# 2_DDR3L_16bits.net
KiCad netlist of a schematic drawn in Altium Designer
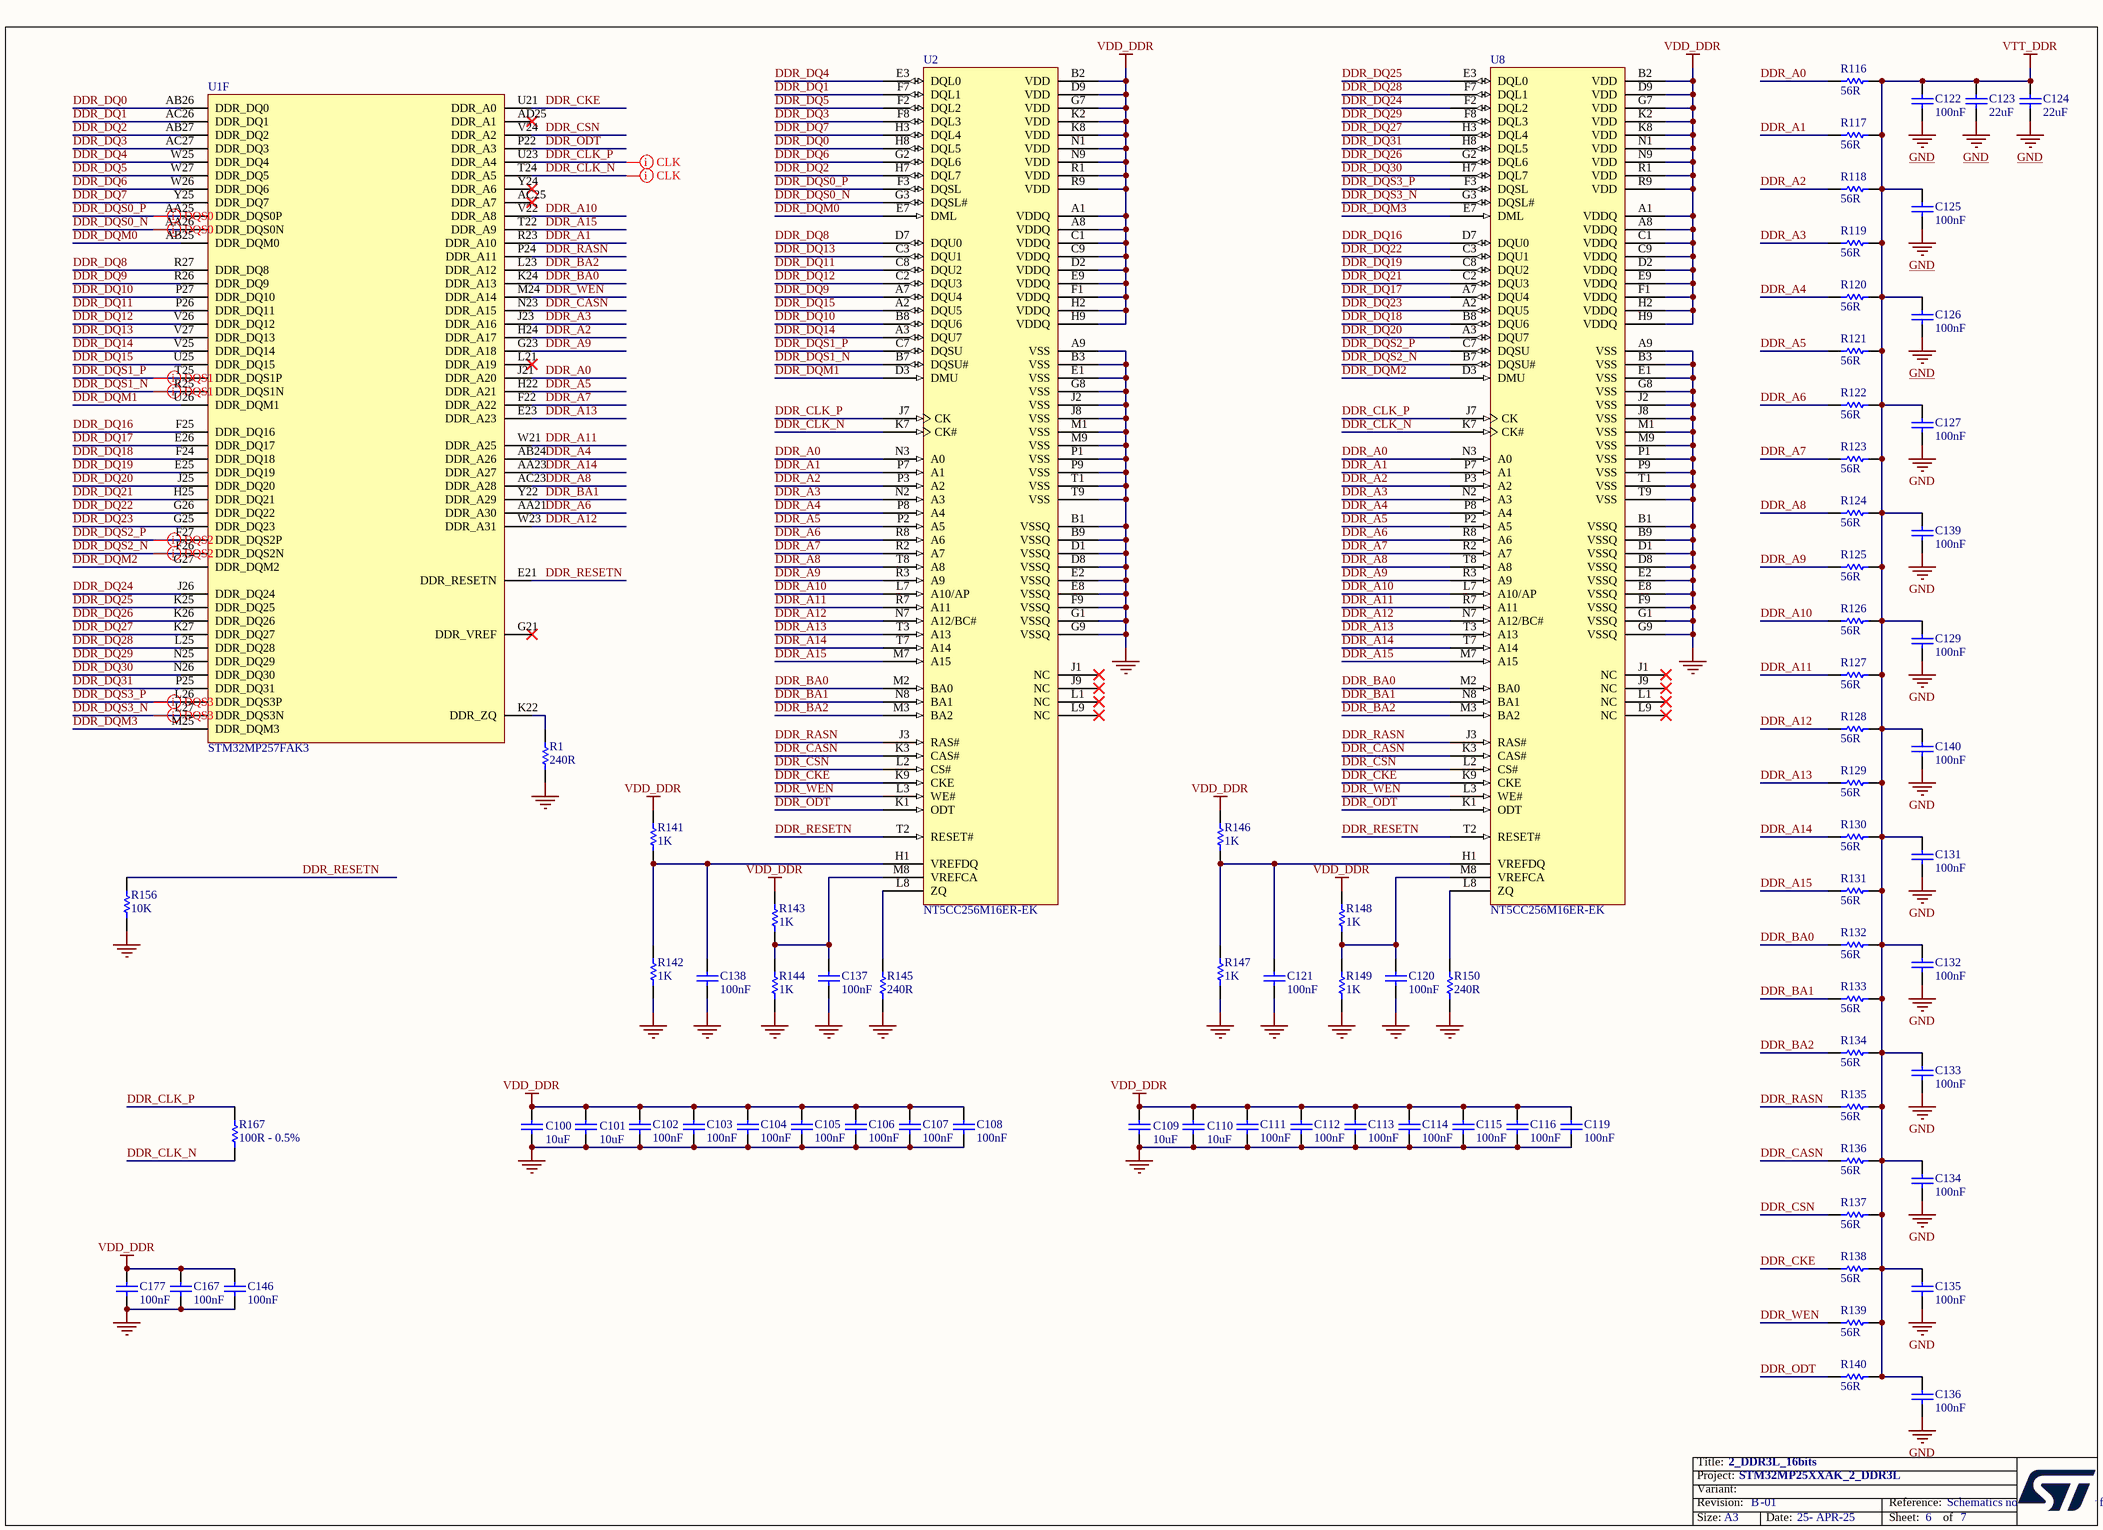
[diagram p0: 2_DDR3L_16bits.SchDoc]

(export (version "E")
  (design (tool "Eeschema 10.0.6"))
  (components
    (comp (ref "C100")
      (value "10uF")
      (footprint "C0603")
      (description "Capacitor, MLCC, 10uF, 10V, X5R, +/-10%, 0603, T=0.8mm")
      (fields
        (field (name "INTERNAL_PART_NUMBER") "MCD-00099")
        (field (name "MANUFACTURER_PART_NUMBER") "GRM188R61A106KE69D")
      )
      (libsource (lib "MCD_PARTS_database") (part "Capacitor"))
    )
    (comp (ref "C101")
      (value "10uF")
      (footprint "C0603")
      (description "Capacitor, MLCC, 10uF, 10V, X5R, +/-10%, 0603, T=0.8mm")
      (fields
        (field (name "INTERNAL_PART_NUMBER") "MCD-00099")
        (field (name "MANUFACTURER_PART_NUMBER") "GRM188R61A106KE69D")
      )
      (libsource (lib "MCD_PARTS_database") (part "Capacitor"))
    )
    (comp (ref "C102")
      (value "100nF")
      (footprint "C0402")
      (description "Capacitor, MLCC, 100nF, 16V, X7R, +/-10%, 0402, T=0.5mm")
      (fields (field (name "INTERNAL_PART_NUMBER") "MCD-00006") (field (name "MANUFACTURER") "YAGEO"))
      (libsource (lib "MCD_PARTS_database") (part "Capacitor"))
    )
    (comp (ref "C103")
      (value "100nF")
      (footprint "C0402")
      (description "Capacitor, MLCC, 100nF, 16V, X7R, +/-10%, 0402, T=0.5mm")
      (fields (field (name "INTERNAL_PART_NUMBER") "MCD-00006") (field (name "MANUFACTURER") "YAGEO"))
      (libsource (lib "MCD_PARTS_database") (part "Capacitor"))
    )
    (comp (ref "C104")
      (value "100nF")
      (footprint "C0402")
      (description "Capacitor, MLCC, 100nF, 16V, X7R, +/-10%, 0402, T=0.5mm")
      (fields (field (name "INTERNAL_PART_NUMBER") "MCD-00006") (field (name "MANUFACTURER") "YAGEO"))
      (libsource (lib "MCD_PARTS_database") (part "Capacitor"))
    )
    (comp (ref "C105")
      (value "100nF")
      (footprint "C0402")
      (description "Capacitor, MLCC, 100nF, 16V, X7R, +/-10%, 0402, T=0.5mm")
      (fields (field (name "INTERNAL_PART_NUMBER") "MCD-00006") (field (name "MANUFACTURER") "YAGEO"))
      (libsource (lib "MCD_PARTS_database") (part "Capacitor"))
    )
    (comp (ref "C106")
      (value "100nF")
      (footprint "C0402")
      (description "Capacitor, MLCC, 100nF, 16V, X7R, +/-10%, 0402, T=0.5mm")
      (fields (field (name "INTERNAL_PART_NUMBER") "MCD-00006") (field (name "MANUFACTURER") "YAGEO"))
      (libsource (lib "MCD_PARTS_database") (part "Capacitor"))
    )
    (comp (ref "C107")
      (value "100nF")
      (footprint "C0402")
      (description "Capacitor, MLCC, 100nF, 16V, X7R, +/-10%, 0402, T=0.5mm")
      (fields (field (name "INTERNAL_PART_NUMBER") "MCD-00006") (field (name "MANUFACTURER") "YAGEO"))
      (libsource (lib "MCD_PARTS_database") (part "Capacitor"))
    )
    (comp (ref "C108")
      (value "100nF")
      (footprint "C0402")
      (description "Capacitor, MLCC, 100nF, 16V, X7R, +/-10%, 0402, T=0.5mm")
      (fields (field (name "INTERNAL_PART_NUMBER") "MCD-00006") (field (name "MANUFACTURER") "YAGEO"))
      (libsource (lib "MCD_PARTS_database") (part "Capacitor"))
    )
    (comp (ref "C109")
      (value "10uF")
      (footprint "C0603")
      (description "Capacitor, MLCC, 10uF, 10V, X5R, +/-10%, 0603, T=0.8mm")
      (fields
        (field (name "INTERNAL_PART_NUMBER") "MCD-00099")
        (field (name "MANUFACTURER_PART_NUMBER") "GRM188R61A106KE69D")
      )
      (libsource (lib "MCD_PARTS_database") (part "Capacitor"))
    )
    (comp (ref "C110")
      (value "10uF")
      (footprint "C0603")
      (description "Capacitor, MLCC, 10uF, 10V, X5R, +/-10%, 0603, T=0.8mm")
      (fields
        (field (name "INTERNAL_PART_NUMBER") "MCD-00099")
        (field (name "MANUFACTURER_PART_NUMBER") "GRM188R61A106KE69D")
      )
      (libsource (lib "MCD_PARTS_database") (part "Capacitor"))
    )
    (comp (ref "C111")
      (value "100nF")
      (footprint "C0402")
      (description "Capacitor, MLCC, 100nF, 16V, X7R, +/-10%, 0402, T=0.5mm")
      (fields (field (name "INTERNAL_PART_NUMBER") "MCD-00006") (field (name "MANUFACTURER") "YAGEO"))
      (libsource (lib "MCD_PARTS_database") (part "Capacitor"))
    )
    (comp (ref "C112")
      (value "100nF")
      (footprint "C0402")
      (description "Capacitor, MLCC, 100nF, 16V, X7R, +/-10%, 0402, T=0.5mm")
      (fields (field (name "INTERNAL_PART_NUMBER") "MCD-00006") (field (name "MANUFACTURER") "YAGEO"))
      (libsource (lib "MCD_PARTS_database") (part "Capacitor"))
    )
    (comp (ref "C113")
      (value "100nF")
      (footprint "C0402")
      (description "Capacitor, MLCC, 100nF, 16V, X7R, +/-10%, 0402, T=0.5mm")
      (fields (field (name "INTERNAL_PART_NUMBER") "MCD-00006") (field (name "MANUFACTURER") "YAGEO"))
      (libsource (lib "MCD_PARTS_database") (part "Capacitor"))
    )
    (comp (ref "C114")
      (value "100nF")
      (footprint "C0402")
      (description "Capacitor, MLCC, 100nF, 16V, X7R, +/-10%, 0402, T=0.5mm")
      (fields (field (name "INTERNAL_PART_NUMBER") "MCD-00006") (field (name "MANUFACTURER") "YAGEO"))
      (libsource (lib "MCD_PARTS_database") (part "Capacitor"))
    )
    (comp (ref "C115")
      (value "100nF")
      (footprint "C0402")
      (description "Capacitor, MLCC, 100nF, 16V, X7R, +/-10%, 0402, T=0.5mm")
      (fields (field (name "INTERNAL_PART_NUMBER") "MCD-00006") (field (name "MANUFACTURER") "YAGEO"))
      (libsource (lib "MCD_PARTS_database") (part "Capacitor"))
    )
    (comp (ref "C116")
      (value "100nF")
      (footprint "C0402")
      (description "Capacitor, MLCC, 100nF, 16V, X7R, +/-10%, 0402, T=0.5mm")
      (fields (field (name "INTERNAL_PART_NUMBER") "MCD-00006") (field (name "MANUFACTURER") "YAGEO"))
      (libsource (lib "MCD_PARTS_database") (part "Capacitor"))
    )
    (comp (ref "C119")
      (value "100nF")
      (footprint "C0402")
      (description "Capacitor, MLCC, 100nF, 16V, X7R, +/-10%, 0402, T=0.5mm")
      (fields (field (name "INTERNAL_PART_NUMBER") "MCD-00006") (field (name "MANUFACTURER") "YAGEO"))
      (libsource (lib "MCD_PARTS_database") (part "Capacitor"))
    )
    (comp (ref "C120")
      (value "100nF")
      (footprint "C0402")
      (description "Capacitor, MLCC, 100nF, 16V, X7R, +/-10%, 0402, T=0.5mm")
      (fields (field (name "INTERNAL_PART_NUMBER") "MCD-00006") (field (name "MANUFACTURER") "YAGEO"))
      (libsource (lib "MCD_PARTS_database") (part "Capacitor"))
    )
    (comp (ref "C121")
      (value "100nF")
      (footprint "C0402")
      (description "Capacitor, MLCC, 100nF, 16V, X7R, +/-10%, 0402, T=0.5mm")
      (fields (field (name "INTERNAL_PART_NUMBER") "MCD-00006") (field (name "MANUFACTURER") "YAGEO"))
      (libsource (lib "MCD_PARTS_database") (part "Capacitor"))
    )
    (comp (ref "C122")
      (value "100nF")
      (footprint "C0402")
      (description "Capacitor, MLCC, 100nF, 16V, X7R, +/-10%, 0402, T=0.5mm")
      (fields (field (name "INTERNAL_PART_NUMBER") "MCD-00006") (field (name "MANUFACTURER") "YAGEO"))
      (libsource (lib "MCD_PARTS_database") (part "Capacitor"))
    )
    (comp (ref "C123")
      (value "22uF")
      (footprint "C0603")
      (description "Capacitor, MLCC, 22uF, 6V3, X5R, +/-20%, 0603, T=0,8mm")
      (fields (field (name "INTERNAL_PART_NUMBER") "MCD-00100") (field (name "MANUFACTURER") "MURATA"))
      (libsource (lib "MCD_PARTS_database") (part "Capacitor"))
    )
    (comp (ref "C124")
      (value "22uF")
      (footprint "C0603")
      (description "Capacitor, MLCC, 22uF, 6V3, X5R, +/-20%, 0603, T=0,8mm")
      (fields (field (name "INTERNAL_PART_NUMBER") "MCD-00100") (field (name "MANUFACTURER") "MURATA"))
      (libsource (lib "MCD_PARTS_database") (part "Capacitor"))
    )
    (comp (ref "C125")
      (value "100nF")
      (footprint "C0402")
      (description "Capacitor, MLCC, 100nF, 16V, X7R, +/-10%, 0402, T=0.5mm")
      (fields (field (name "INTERNAL_PART_NUMBER") "MCD-00006") (field (name "MANUFACTURER") "YAGEO"))
      (libsource (lib "MCD_PARTS_database") (part "Capacitor"))
    )
    (comp (ref "C126")
      (value "100nF")
      (footprint "C0402")
      (description "Capacitor, MLCC, 100nF, 16V, X7R, +/-10%, 0402, T=0.5mm")
      (fields (field (name "INTERNAL_PART_NUMBER") "MCD-00006") (field (name "MANUFACTURER") "YAGEO"))
      (libsource (lib "MCD_PARTS_database") (part "Capacitor"))
    )
    (comp (ref "C127")
      (value "100nF")
      (footprint "C0402")
      (description "Capacitor, MLCC, 100nF, 16V, X7R, +/-10%, 0402, T=0.5mm")
      (fields (field (name "INTERNAL_PART_NUMBER") "MCD-00006") (field (name "MANUFACTURER") "YAGEO"))
      (libsource (lib "MCD_PARTS_database") (part "Capacitor"))
    )
    (comp (ref "C129")
      (value "100nF")
      (footprint "C0402")
      (description "Capacitor, MLCC, 100nF, 16V, X7R, +/-10%, 0402, T=0.5mm")
      (fields (field (name "INTERNAL_PART_NUMBER") "MCD-00006") (field (name "MANUFACTURER") "YAGEO"))
      (libsource (lib "MCD_PARTS_database") (part "Capacitor"))
    )
    (comp (ref "C131")
      (value "100nF")
      (footprint "C0402")
      (description "Capacitor, MLCC, 100nF, 16V, X7R, +/-10%, 0402, T=0.5mm")
      (fields (field (name "INTERNAL_PART_NUMBER") "MCD-00006") (field (name "MANUFACTURER") "YAGEO"))
      (libsource (lib "MCD_PARTS_database") (part "Capacitor"))
    )
    (comp (ref "C132")
      (value "100nF")
      (footprint "C0402")
      (description "Capacitor, MLCC, 100nF, 16V, X7R, +/-10%, 0402, T=0.5mm")
      (fields (field (name "INTERNAL_PART_NUMBER") "MCD-00006") (field (name "MANUFACTURER") "YAGEO"))
      (libsource (lib "MCD_PARTS_database") (part "Capacitor"))
    )
    (comp (ref "C133")
      (value "100nF")
      (footprint "C0402")
      (description "Capacitor, MLCC, 100nF, 16V, X7R, +/-10%, 0402, T=0.5mm")
      (fields (field (name "INTERNAL_PART_NUMBER") "MCD-00006") (field (name "MANUFACTURER") "YAGEO"))
      (libsource (lib "MCD_PARTS_database") (part "Capacitor"))
    )
    (comp (ref "C134")
      (value "100nF")
      (footprint "C0402")
      (description "Capacitor, MLCC, 100nF, 16V, X7R, +/-10%, 0402, T=0.5mm")
      (fields (field (name "INTERNAL_PART_NUMBER") "MCD-00006") (field (name "MANUFACTURER") "YAGEO"))
      (libsource (lib "MCD_PARTS_database") (part "Capacitor"))
    )
    (comp (ref "C135")
      (value "100nF")
      (footprint "C0402")
      (description "Capacitor, MLCC, 100nF, 16V, X7R, +/-10%, 0402, T=0.5mm")
      (fields (field (name "INTERNAL_PART_NUMBER") "MCD-00006") (field (name "MANUFACTURER") "YAGEO"))
      (libsource (lib "MCD_PARTS_database") (part "Capacitor"))
    )
    (comp (ref "C136")
      (value "100nF")
      (footprint "C0402")
      (description "Capacitor, MLCC, 100nF, 16V, X7R, +/-10%, 0402, T=0.5mm")
      (fields (field (name "INTERNAL_PART_NUMBER") "MCD-00006") (field (name "MANUFACTURER") "YAGEO"))
      (libsource (lib "MCD_PARTS_database") (part "Capacitor"))
    )
    (comp (ref "C137")
      (value "100nF")
      (footprint "C0402")
      (description "Capacitor, MLCC, 100nF, 16V, X7R, +/-10%, 0402, T=0.5mm")
      (fields (field (name "INTERNAL_PART_NUMBER") "MCD-00006") (field (name "MANUFACTURER") "YAGEO"))
      (libsource (lib "MCD_PARTS_database") (part "Capacitor"))
    )
    (comp (ref "C138")
      (value "100nF")
      (footprint "C0402")
      (description "Capacitor, MLCC, 100nF, 16V, X7R, +/-10%, 0402, T=0.5mm")
      (fields (field (name "INTERNAL_PART_NUMBER") "MCD-00006") (field (name "MANUFACTURER") "YAGEO"))
      (libsource (lib "MCD_PARTS_database") (part "Capacitor"))
    )
    (comp (ref "C139")
      (value "100nF")
      (footprint "C0402")
      (description "Capacitor, MLCC, 100nF, 16V, X7R, +/-10%, 0402, T=0.5mm")
      (fields (field (name "INTERNAL_PART_NUMBER") "MCD-00006") (field (name "MANUFACTURER") "YAGEO"))
      (libsource (lib "MCD_PARTS_database") (part "Capacitor"))
    )
    (comp (ref "C140")
      (value "100nF")
      (footprint "C0402")
      (description "Capacitor, MLCC, 100nF, 16V, X7R, +/-10%, 0402, T=0.5mm")
      (fields (field (name "INTERNAL_PART_NUMBER") "MCD-00006") (field (name "MANUFACTURER") "YAGEO"))
      (libsource (lib "MCD_PARTS_database") (part "Capacitor"))
    )
    (comp (ref "C146")
      (value "100nF")
      (footprint "C0402")
      (description "Capacitor, MLCC, 100nF, 16V, X7R, +/-10%, 0402, T=0.5mm")
      (fields (field (name "INTERNAL_PART_NUMBER") "MCD-00006") (field (name "MANUFACTURER") "YAGEO"))
      (libsource (lib "MCD_PARTS_database") (part "Capacitor"))
    )
    (comp (ref "C167")
      (value "100nF")
      (footprint "C0402")
      (description "Capacitor, MLCC, 100nF, 16V, X7R, +/-10%, 0402, T=0.5mm")
      (fields (field (name "INTERNAL_PART_NUMBER") "MCD-00006") (field (name "MANUFACTURER") "YAGEO"))
      (libsource (lib "MCD_PARTS_database") (part "Capacitor"))
    )
    (comp (ref "C177")
      (value "100nF")
      (footprint "C0402")
      (description "Capacitor, MLCC, 100nF, 16V, X7R, +/-10%, 0402, T=0.5mm")
      (fields (field (name "INTERNAL_PART_NUMBER") "MCD-00006") (field (name "MANUFACTURER") "YAGEO"))
      (libsource (lib "MCD_PARTS_database") (part "Capacitor"))
    )
    (comp (ref "R1")
      (value "240R")
      (footprint "R0201_H0P23")
      (description "Resistor, 240R, 0201, +/-1%, 1/20W")
      (fields (field (name "INTERNAL_PART_NUMBER") "MCD-02253") (field (name "MANUFACTURER") "YAGEO"))
      (libsource (lib "MCD_PARTS_database") (part "Resistor"))
    )
    (comp (ref "R116")
      (value "56R")
      (footprint "R0402")
      (description "Resistor, 56R, 0402, +/-1%, 1/16W")
      (fields (field (name "INTERNAL_PART_NUMBER") "MCD-00054") (field (name "MANUFACTURER") "YAGEO"))
      (libsource (lib "MCD_PARTS_database") (part "Resistor"))
    )
    (comp (ref "R117")
      (value "56R")
      (footprint "R0402")
      (description "Resistor, 56R, 0402, +/-1%, 1/16W")
      (fields (field (name "INTERNAL_PART_NUMBER") "MCD-00054") (field (name "MANUFACTURER") "YAGEO"))
      (libsource (lib "MCD_PARTS_database") (part "Resistor"))
    )
    (comp (ref "R118")
      (value "56R")
      (footprint "R0402")
      (description "Resistor, 56R, 0402, +/-1%, 1/16W")
      (fields (field (name "INTERNAL_PART_NUMBER") "MCD-00054") (field (name "MANUFACTURER") "YAGEO"))
      (libsource (lib "MCD_PARTS_database") (part "Resistor"))
    )
    (comp (ref "R119")
      (value "56R")
      (footprint "R0402")
      (description "Resistor, 56R, 0402, +/-1%, 1/16W")
      (fields (field (name "INTERNAL_PART_NUMBER") "MCD-00054") (field (name "MANUFACTURER") "YAGEO"))
      (libsource (lib "MCD_PARTS_database") (part "Resistor"))
    )
    (comp (ref "R120")
      (value "56R")
      (footprint "R0402")
      (description "Resistor, 56R, 0402, +/-1%, 1/16W")
      (fields (field (name "INTERNAL_PART_NUMBER") "MCD-00054") (field (name "MANUFACTURER") "YAGEO"))
      (libsource (lib "MCD_PARTS_database") (part "Resistor"))
    )
    (comp (ref "R121")
      (value "56R")
      (footprint "R0402")
      (description "Resistor, 56R, 0402, +/-1%, 1/16W")
      (fields (field (name "INTERNAL_PART_NUMBER") "MCD-00054") (field (name "MANUFACTURER") "YAGEO"))
      (libsource (lib "MCD_PARTS_database") (part "Resistor"))
    )
    (comp (ref "R122")
      (value "56R")
      (footprint "R0402")
      (description "Resistor, 56R, 0402, +/-1%, 1/16W")
      (fields (field (name "INTERNAL_PART_NUMBER") "MCD-00054") (field (name "MANUFACTURER") "YAGEO"))
      (libsource (lib "MCD_PARTS_database") (part "Resistor"))
    )
    (comp (ref "R123")
      (value "56R")
      (footprint "R0402")
      (description "Resistor, 56R, 0402, +/-1%, 1/16W")
      (fields (field (name "INTERNAL_PART_NUMBER") "MCD-00054") (field (name "MANUFACTURER") "YAGEO"))
      (libsource (lib "MCD_PARTS_database") (part "Resistor"))
    )
    (comp (ref "R124")
      (value "56R")
      (footprint "R0402")
      (description "Resistor, 56R, 0402, +/-1%, 1/16W")
      (fields (field (name "INTERNAL_PART_NUMBER") "MCD-00054") (field (name "MANUFACTURER") "YAGEO"))
      (libsource (lib "MCD_PARTS_database") (part "Resistor"))
    )
    (comp (ref "R125")
      (value "56R")
      (footprint "R0402")
      (description "Resistor, 56R, 0402, +/-1%, 1/16W")
      (fields (field (name "INTERNAL_PART_NUMBER") "MCD-00054") (field (name "MANUFACTURER") "YAGEO"))
      (libsource (lib "MCD_PARTS_database") (part "Resistor"))
    )
    (comp (ref "R126")
      (value "56R")
      (footprint "R0402")
      (description "Resistor, 56R, 0402, +/-1%, 1/16W")
      (fields (field (name "INTERNAL_PART_NUMBER") "MCD-00054") (field (name "MANUFACTURER") "YAGEO"))
      (libsource (lib "MCD_PARTS_database") (part "Resistor"))
    )
    (comp (ref "R127")
      (value "56R")
      (footprint "R0402")
      (description "Resistor, 56R, 0402, +/-1%, 1/16W")
      (fields (field (name "INTERNAL_PART_NUMBER") "MCD-00054") (field (name "MANUFACTURER") "YAGEO"))
      (libsource (lib "MCD_PARTS_database") (part "Resistor"))
    )
    (comp (ref "R128")
      (value "56R")
      (footprint "R0402")
      (description "Resistor, 56R, 0402, +/-1%, 1/16W")
      (fields (field (name "INTERNAL_PART_NUMBER") "MCD-00054") (field (name "MANUFACTURER") "YAGEO"))
      (libsource (lib "MCD_PARTS_database") (part "Resistor"))
    )
    (comp (ref "R129")
      (value "56R")
      (footprint "R0402")
      (description "Resistor, 56R, 0402, +/-1%, 1/16W")
      (fields (field (name "INTERNAL_PART_NUMBER") "MCD-00054") (field (name "MANUFACTURER") "YAGEO"))
      (libsource (lib "MCD_PARTS_database") (part "Resistor"))
    )
    (comp (ref "R130")
      (value "56R")
      (footprint "R0402")
      (description "Resistor, 56R, 0402, +/-1%, 1/16W")
      (fields (field (name "INTERNAL_PART_NUMBER") "MCD-00054") (field (name "MANUFACTURER") "YAGEO"))
      (libsource (lib "MCD_PARTS_database") (part "Resistor"))
    )
    (comp (ref "R131")
      (value "56R")
      (footprint "R0402")
      (description "Resistor, 56R, 0402, +/-1%, 1/16W")
      (fields (field (name "INTERNAL_PART_NUMBER") "MCD-00054") (field (name "MANUFACTURER") "YAGEO"))
      (libsource (lib "MCD_PARTS_database") (part "Resistor"))
    )
    (comp (ref "R132")
      (value "56R")
      (footprint "R0402")
      (description "Resistor, 56R, 0402, +/-1%, 1/16W")
      (fields (field (name "INTERNAL_PART_NUMBER") "MCD-00054") (field (name "MANUFACTURER") "YAGEO"))
      (libsource (lib "MCD_PARTS_database") (part "Resistor"))
    )
    (comp (ref "R133")
      (value "56R")
      (footprint "R0402")
      (description "Resistor, 56R, 0402, +/-1%, 1/16W")
      (fields (field (name "INTERNAL_PART_NUMBER") "MCD-00054") (field (name "MANUFACTURER") "YAGEO"))
      (libsource (lib "MCD_PARTS_database") (part "Resistor"))
    )
    (comp (ref "R134")
      (value "56R")
      (footprint "R0402")
      (description "Resistor, 56R, 0402, +/-1%, 1/16W")
      (fields (field (name "INTERNAL_PART_NUMBER") "MCD-00054") (field (name "MANUFACTURER") "YAGEO"))
      (libsource (lib "MCD_PARTS_database") (part "Resistor"))
    )
    (comp (ref "R135")
      (value "56R")
      (footprint "R0402")
      (description "Resistor, 56R, 0402, +/-1%, 1/16W")
      (fields (field (name "INTERNAL_PART_NUMBER") "MCD-00054") (field (name "MANUFACTURER") "YAGEO"))
      (libsource (lib "MCD_PARTS_database") (part "Resistor"))
    )
    (comp (ref "R136")
      (value "56R")
      (footprint "R0402")
      (description "Resistor, 56R, 0402, +/-1%, 1/16W")
      (fields (field (name "INTERNAL_PART_NUMBER") "MCD-00054") (field (name "MANUFACTURER") "YAGEO"))
      (libsource (lib "MCD_PARTS_database") (part "Resistor"))
    )
    (comp (ref "R137")
      (value "56R")
      (footprint "R0402")
      (description "Resistor, 56R, 0402, +/-1%, 1/16W")
      (fields (field (name "INTERNAL_PART_NUMBER") "MCD-00054") (field (name "MANUFACTURER") "YAGEO"))
      (libsource (lib "MCD_PARTS_database") (part "Resistor"))
    )
    (comp (ref "R138")
      (value "56R")
      (footprint "R0402")
      (description "Resistor, 56R, 0402, +/-1%, 1/16W")
      (fields (field (name "INTERNAL_PART_NUMBER") "MCD-00054") (field (name "MANUFACTURER") "YAGEO"))
      (libsource (lib "MCD_PARTS_database") (part "Resistor"))
    )
    (comp (ref "R139")
      (value "56R")
      (footprint "R0402")
      (description "Resistor, 56R, 0402, +/-1%, 1/16W")
      (fields (field (name "INTERNAL_PART_NUMBER") "MCD-00054") (field (name "MANUFACTURER") "YAGEO"))
      (libsource (lib "MCD_PARTS_database") (part "Resistor"))
    )
    (comp (ref "R140")
      (value "56R")
      (footprint "R0402")
      (description "Resistor, 56R, 0402, +/-1%, 1/16W")
      (fields (field (name "INTERNAL_PART_NUMBER") "MCD-00054") (field (name "MANUFACTURER") "YAGEO"))
      (libsource (lib "MCD_PARTS_database") (part "Resistor"))
    )
    (comp (ref "R141")
      (value "1K")
      (footprint "R0402")
      (description "Resistor, 1K, 0402, +/-1%,1/16W")
      (fields (field (name "INTERNAL_PART_NUMBER") "MCD-00061") (field (name "MANUFACTURER") "YAGEO"))
      (libsource (lib "MCD_PARTS_database") (part "Resistor"))
    )
    (comp (ref "R142")
      (value "1K")
      (footprint "R0402")
      (description "Resistor, 1K, 0402, +/-1%,1/16W")
      (fields (field (name "INTERNAL_PART_NUMBER") "MCD-00061") (field (name "MANUFACTURER") "YAGEO"))
      (libsource (lib "MCD_PARTS_database") (part "Resistor"))
    )
    (comp (ref "R143")
      (value "1K")
      (footprint "R0402")
      (description "Resistor, 1K, 0402, +/-1%,1/16W")
      (fields (field (name "INTERNAL_PART_NUMBER") "MCD-00061") (field (name "MANUFACTURER") "YAGEO"))
      (libsource (lib "MCD_PARTS_database") (part "Resistor"))
    )
    (comp (ref "R144")
      (value "1K")
      (footprint "R0402")
      (description "Resistor, 1K, 0402, +/-1%,1/16W")
      (fields (field (name "INTERNAL_PART_NUMBER") "MCD-00061") (field (name "MANUFACTURER") "YAGEO"))
      (libsource (lib "MCD_PARTS_database") (part "Resistor"))
    )
    (comp (ref "R145")
      (value "240R")
      (footprint "R0402")
      (description "Resistor,240R,0402,1%,1/16W")
      (fields (field (name "INTERNAL_PART_NUMBER") "MCD-00120") (field (name "MANUFACTURER") "YAGEO"))
      (libsource (lib "MCD_PARTS_database") (part "Resistor"))
    )
    (comp (ref "R146")
      (value "1K")
      (footprint "R0402")
      (description "Resistor, 1K, 0402, +/-1%,1/16W")
      (fields (field (name "INTERNAL_PART_NUMBER") "MCD-00061") (field (name "MANUFACTURER") "YAGEO"))
      (libsource (lib "MCD_PARTS_database") (part "Resistor"))
    )
    (comp (ref "R147")
      (value "1K")
      (footprint "R0402")
      (description "Resistor, 1K, 0402, +/-1%,1/16W")
      (fields (field (name "INTERNAL_PART_NUMBER") "MCD-00061") (field (name "MANUFACTURER") "YAGEO"))
      (libsource (lib "MCD_PARTS_database") (part "Resistor"))
    )
    (comp (ref "R148")
      (value "1K")
      (footprint "R0402")
      (description "Resistor, 1K, 0402, +/-1%,1/16W")
      (fields (field (name "INTERNAL_PART_NUMBER") "MCD-00061") (field (name "MANUFACTURER") "YAGEO"))
      (libsource (lib "MCD_PARTS_database") (part "Resistor"))
    )
    (comp (ref "R149")
      (value "1K")
      (footprint "R0402")
      (description "Resistor, 1K, 0402, +/-1%,1/16W")
      (fields (field (name "INTERNAL_PART_NUMBER") "MCD-00061") (field (name "MANUFACTURER") "YAGEO"))
      (libsource (lib "MCD_PARTS_database") (part "Resistor"))
    )
    (comp (ref "R150")
      (value "240R")
      (footprint "R0402")
      (description "Resistor,240R,0402,1%,1/16W")
      (fields (field (name "INTERNAL_PART_NUMBER") "MCD-00120") (field (name "MANUFACTURER") "YAGEO"))
      (libsource (lib "MCD_PARTS_database") (part "Resistor"))
    )
    (comp (ref "R156")
      (value "10K")
      (footprint "R0402")
      (description "Resistor,10K,0402,1%,1/16W")
      (fields (field (name "INTERNAL_PART_NUMBER") "MCD-00053") (field (name "BMS_PART_NUMBER") "9131590"))
      (libsource (lib "MCD_PARTS_database") (part "Resistor"))
    )
    (comp (ref "R167")
      (value "100R - 0.5%")
      (footprint "R0402")
      (description "Resistor,100R,0402,0,5%,1/16W,±100ppm/°C")
      (fields (field (name "INTERNAL_PART_NUMBER") "MCD-01819") (field (name "MANUFACTURER") "YAGEO"))
      (libsource (lib "MCD_PARTS_database") (part "Resistor"))
    )
    (comp (ref "U1")
      (value "STM32MP257FAK3")
      (footprint "ICC_TFBGA424_14X14_P050_H1P20_CODE-B0A2")
      (description "MPU , 2xCortex-A35@1.5GHz, Cortex-M33@400MHz, TFBGA 14x14, pitch 0.5, 648KB SRAM, With Crypto")
      (fields
        (field (name "INTERNAL_PART_NUMBER") "MCD-03375")
        (field (name "MANUFACTURER") "STMICROELECTRONICS")
      )
      (libsource (lib "MCD_PARTS_database") (part "STM32MP257FAK3"))
    )
    (comp (ref "U2")
      (value "NT5CC256M16ER-EK")
      (footprint "ICC_VFBGA96_9x13_P080")
      (description "Memory,DDR3L,4Gb,256Mbx16,933Mhz,1V35,TFBGA")
      (fields (field (name "INTERNAL_PART_NUMBER") "MCD-01811") (field (name "BMS_PART_NUMBER") "9171435"))
      (libsource (lib "MCD_PARTS_database") (part "NT5CC256M16ER-EK"))
    )
    (comp (ref "U8")
      (value "NT5CC256M16ER-EK")
      (footprint "ICC_VFBGA96_9x13_P080")
      (description "Memory,DDR3L,4Gb,256Mbx16,933Mhz,1V35,TFBGA")
      (fields (field (name "INTERNAL_PART_NUMBER") "MCD-01811") (field (name "BMS_PART_NUMBER") "9171435"))
      (libsource (lib "MCD_PARTS_database") (part "NT5CC256M16ER-EK"))
    )
  )
  (nets
    (net (code "1") (name "/DDR_A0") (class "Default")
      (node (ref "R116") (pin "1") (pinfunction "1_1") (pintype "passive"))
      (node (ref "U1") (pin "J21") (pinfunction "DDR_A20_J21") (pintype "passive"))
      (node (ref "U2") (pin "N3") (pinfunction "A0_N3") (pintype "input"))
      (node (ref "U8") (pin "N3") (pinfunction "A0_N3") (pintype "input"))
    )
    (net (code "2") (name "/DDR_A1") (class "Default")
      (node (ref "R117") (pin "1") (pinfunction "1_1") (pintype "passive"))
      (node (ref "U1") (pin "R23") (pinfunction "DDR_A10_R23") (pintype "passive"))
      (node (ref "U2") (pin "P7") (pinfunction "A1_P7") (pintype "input"))
      (node (ref "U8") (pin "P7") (pinfunction "A1_P7") (pintype "input"))
    )
    (net (code "3") (name "/DDR_A2") (class "Default")
      (node (ref "R118") (pin "1") (pinfunction "1_1") (pintype "passive"))
      (node (ref "U1") (pin "H24") (pinfunction "DDR_A17_H24") (pintype "passive"))
      (node (ref "U2") (pin "P3") (pinfunction "A2_P3") (pintype "input"))
      (node (ref "U8") (pin "P3") (pinfunction "A2_P3") (pintype "input"))
    )
    (net (code "4") (name "/DDR_A3") (class "Default")
      (node (ref "R119") (pin "1") (pinfunction "1_1") (pintype "passive"))
      (node (ref "U1") (pin "J23") (pinfunction "DDR_A16_J23") (pintype "passive"))
      (node (ref "U2") (pin "N2") (pinfunction "A3_N2") (pintype "input"))
      (node (ref "U8") (pin "N2") (pinfunction "A3_N2") (pintype "input"))
    )
    (net (code "5") (name "/DDR_A4") (class "Default")
      (node (ref "R120") (pin "1") (pinfunction "1_1") (pintype "passive"))
      (node (ref "U1") (pin "AB24") (pinfunction "DDR_A26_AB24") (pintype "passive"))
      (node (ref "U2") (pin "P8") (pinfunction "A4_P8") (pintype "input"))
      (node (ref "U8") (pin "P8") (pinfunction "A4_P8") (pintype "input"))
    )
    (net (code "6") (name "/DDR_A5") (class "Default")
      (node (ref "R121") (pin "1") (pinfunction "1_1") (pintype "passive"))
      (node (ref "U1") (pin "H22") (pinfunction "DDR_A21_H22") (pintype "passive"))
      (node (ref "U2") (pin "P2") (pinfunction "A5_P2") (pintype "input"))
      (node (ref "U8") (pin "P2") (pinfunction "A5_P2") (pintype "input"))
    )
    (net (code "7") (name "/DDR_A6") (class "Default")
      (node (ref "R122") (pin "1") (pinfunction "1_1") (pintype "passive"))
      (node (ref "U1") (pin "AA21") (pinfunction "DDR_A30_AA21") (pintype "passive"))
      (node (ref "U2") (pin "R8") (pinfunction "A6_R8") (pintype "input"))
      (node (ref "U8") (pin "R8") (pinfunction "A6_R8") (pintype "input"))
    )
    (net (code "8") (name "/DDR_A7") (class "Default")
      (node (ref "R123") (pin "1") (pinfunction "1_1") (pintype "passive"))
      (node (ref "U1") (pin "F22") (pinfunction "DDR_A22_F22") (pintype "passive"))
      (node (ref "U2") (pin "R2") (pinfunction "A7_R2") (pintype "input"))
      (node (ref "U8") (pin "R2") (pinfunction "A7_R2") (pintype "input"))
    )
    (net (code "9") (name "/DDR_A8") (class "Default")
      (node (ref "R124") (pin "1") (pinfunction "1_1") (pintype "passive"))
      (node (ref "U1") (pin "AC23") (pinfunction "DDR_A28_AC23") (pintype "passive"))
      (node (ref "U2") (pin "T8") (pinfunction "A8_T8") (pintype "input"))
      (node (ref "U8") (pin "T8") (pinfunction "A8_T8") (pintype "input"))
    )
    (net (code "10") (name "/DDR_A9") (class "Default")
      (node (ref "R125") (pin "1") (pinfunction "1_1") (pintype "passive"))
      (node (ref "U1") (pin "G23") (pinfunction "DDR_A18_G23") (pintype "passive"))
      (node (ref "U2") (pin "R3") (pinfunction "A9_R3") (pintype "input"))
      (node (ref "U8") (pin "R3") (pinfunction "A9_R3") (pintype "input"))
    )
    (net (code "11") (name "/DDR_A10") (class "Default")
      (node (ref "R126") (pin "1") (pinfunction "1_1") (pintype "passive"))
      (node (ref "U1") (pin "V22") (pinfunction "DDR_A8_V22") (pintype "passive"))
      (node (ref "U2") (pin "L7") (pinfunction "A10/AP_L7") (pintype "input"))
      (node (ref "U8") (pin "L7") (pinfunction "A10/AP_L7") (pintype "input"))
    )
    (net (code "12") (name "/DDR_A11") (class "Default")
      (node (ref "R127") (pin "1") (pinfunction "1_1") (pintype "passive"))
      (node (ref "U1") (pin "W21") (pinfunction "DDR_A25_W21") (pintype "passive"))
      (node (ref "U2") (pin "R7") (pinfunction "A11_R7") (pintype "input"))
      (node (ref "U8") (pin "R7") (pinfunction "A11_R7") (pintype "input"))
    )
    (net (code "13") (name "/DDR_A12") (class "Default")
      (node (ref "R128") (pin "1") (pinfunction "1_1") (pintype "passive"))
      (node (ref "U1") (pin "W23") (pinfunction "DDR_A31_W23") (pintype "passive"))
      (node (ref "U2") (pin "N7") (pinfunction "A12/BC#_N7") (pintype "input"))
      (node (ref "U8") (pin "N7") (pinfunction "A12/BC#_N7") (pintype "input"))
    )
    (net (code "14") (name "/DDR_A13") (class "Default")
      (node (ref "R129") (pin "1") (pinfunction "1_1") (pintype "passive"))
      (node (ref "U1") (pin "E23") (pinfunction "DDR_A23_E23") (pintype "passive"))
      (node (ref "U2") (pin "T3") (pinfunction "A13_T3") (pintype "input"))
      (node (ref "U8") (pin "T3") (pinfunction "A13_T3") (pintype "input"))
    )
    (net (code "15") (name "/DDR_A14") (class "Default")
      (node (ref "R130") (pin "1") (pinfunction "1_1") (pintype "passive"))
      (node (ref "U1") (pin "AA23") (pinfunction "DDR_A27_AA23") (pintype "passive"))
      (node (ref "U2") (pin "T7") (pinfunction "A14_T7") (pintype "input"))
      (node (ref "U8") (pin "T7") (pinfunction "A14_T7") (pintype "input"))
    )
    (net (code "16") (name "/DDR_A15") (class "Default")
      (node (ref "R131") (pin "1") (pinfunction "1_1") (pintype "passive"))
      (node (ref "U1") (pin "T22") (pinfunction "DDR_A9_T22") (pintype "passive"))
      (node (ref "U2") (pin "M7") (pinfunction "A15_M7") (pintype "input"))
      (node (ref "U8") (pin "M7") (pinfunction "A15_M7") (pintype "input"))
    )
    (net (code "17") (name "/DDR_BA0") (class "Default")
      (node (ref "R132") (pin "1") (pinfunction "1_1") (pintype "passive"))
      (node (ref "U1") (pin "K24") (pinfunction "DDR_A13_K24") (pintype "passive"))
      (node (ref "U2") (pin "M2") (pinfunction "BA0_M2") (pintype "input"))
      (node (ref "U8") (pin "M2") (pinfunction "BA0_M2") (pintype "input"))
    )
    (net (code "18") (name "/DDR_BA1") (class "Default")
      (node (ref "R133") (pin "1") (pinfunction "1_1") (pintype "passive"))
      (node (ref "U1") (pin "Y22") (pinfunction "DDR_A29_Y22") (pintype "passive"))
      (node (ref "U2") (pin "N8") (pinfunction "BA1_N8") (pintype "input"))
      (node (ref "U8") (pin "N8") (pinfunction "BA1_N8") (pintype "input"))
    )
    (net (code "19") (name "/DDR_BA2") (class "Default")
      (node (ref "R134") (pin "1") (pinfunction "1_1") (pintype "passive"))
      (node (ref "U1") (pin "L23") (pinfunction "DDR_A12_L23") (pintype "passive"))
      (node (ref "U2") (pin "M3") (pinfunction "BA2_M3") (pintype "input"))
      (node (ref "U8") (pin "M3") (pinfunction "BA2_M3") (pintype "input"))
    )
    (net (code "20") (name "/DDR_CASN") (class "Default")
      (node (ref "R136") (pin "1") (pinfunction "1_1") (pintype "passive"))
      (node (ref "U1") (pin "N23") (pinfunction "DDR_A15_N23") (pintype "passive"))
      (node (ref "U2") (pin "K3") (pinfunction "CAS#_K3") (pintype "input"))
      (node (ref "U8") (pin "K3") (pinfunction "CAS#_K3") (pintype "input"))
    )
    (net (code "21") (name "/DDR_CKE") (class "Default")
      (node (ref "R138") (pin "1") (pinfunction "1_1") (pintype "passive"))
      (node (ref "U1") (pin "U21") (pinfunction "DDR_A0_U21") (pintype "passive"))
      (node (ref "U2") (pin "K9") (pinfunction "CKE_K9") (pintype "input"))
      (node (ref "U8") (pin "K9") (pinfunction "CKE_K9") (pintype "input"))
    )
    (net (code "22") (name "/DDR_CLK_N") (class "Default")
      (node (ref "R167") (pin "2") (pinfunction "2_2") (pintype "passive"))
      (node (ref "U1") (pin "T24") (pinfunction "DDR_A5_T24") (pintype "passive"))
      (node (ref "U2") (pin "K7") (pinfunction "CK#_K7") (pintype "input"))
      (node (ref "U8") (pin "K7") (pinfunction "CK#_K7") (pintype "input"))
    )
    (net (code "23") (name "/DDR_CLK_P") (class "Default")
      (node (ref "R167") (pin "1") (pinfunction "1_1") (pintype "passive"))
      (node (ref "U1") (pin "U23") (pinfunction "DDR_A4_U23") (pintype "passive"))
      (node (ref "U2") (pin "J7") (pinfunction "CK_J7") (pintype "input"))
      (node (ref "U8") (pin "J7") (pinfunction "CK_J7") (pintype "input"))
    )
    (net (code "24") (name "/DDR_CSN") (class "Default")
      (node (ref "R137") (pin "1") (pinfunction "1_1") (pintype "passive"))
      (node (ref "U1") (pin "V24") (pinfunction "DDR_A2_V24") (pintype "passive"))
      (node (ref "U2") (pin "L2") (pinfunction "CS#_L2") (pintype "input"))
      (node (ref "U8") (pin "L2") (pinfunction "CS#_L2") (pintype "input"))
    )
    (net (code "25") (name "/DDR_DQ0") (class "Default")
      (node (ref "U1") (pin "AB26") (pinfunction "DDR_DQ0_AB26") (pintype "passive"))
      (node (ref "U2") (pin "H8") (pinfunction "DQL5_H8") (pintype "bidirectional"))
    )
    (net (code "26") (name "/DDR_DQ1") (class "Default")
      (node (ref "U1") (pin "AC26") (pinfunction "DDR_DQ1_AC26") (pintype "passive"))
      (node (ref "U2") (pin "F7") (pinfunction "DQL1_F7") (pintype "bidirectional"))
    )
    (net (code "27") (name "/DDR_DQ2") (class "Default")
      (node (ref "U1") (pin "AB27") (pinfunction "DDR_DQ2_AB27") (pintype "passive"))
      (node (ref "U2") (pin "H7") (pinfunction "DQL7_H7") (pintype "bidirectional"))
    )
    (net (code "28") (name "/DDR_DQ3") (class "Default")
      (node (ref "U1") (pin "AC27") (pinfunction "DDR_DQ3_AC27") (pintype "passive"))
      (node (ref "U2") (pin "F8") (pinfunction "DQL3_F8") (pintype "bidirectional"))
    )
    (net (code "29") (name "/DDR_DQ4") (class "Default")
      (node (ref "U1") (pin "W25") (pinfunction "DDR_DQ4_W25") (pintype "passive"))
      (node (ref "U2") (pin "E3") (pinfunction "DQL0_E3") (pintype "bidirectional"))
    )
    (net (code "30") (name "/DDR_DQ5") (class "Default")
      (node (ref "U1") (pin "W27") (pinfunction "DDR_DQ5_W27") (pintype "passive"))
      (node (ref "U2") (pin "F2") (pinfunction "DQL2_F2") (pintype "bidirectional"))
    )
    (net (code "31") (name "/DDR_DQ6") (class "Default")
      (node (ref "U1") (pin "W26") (pinfunction "DDR_DQ6_W26") (pintype "passive"))
      (node (ref "U2") (pin "G2") (pinfunction "DQL6_G2") (pintype "bidirectional"))
    )
    (net (code "32") (name "/DDR_DQ7") (class "Default")
      (node (ref "U1") (pin "Y25") (pinfunction "DDR_DQ7_Y25") (pintype "passive"))
      (node (ref "U2") (pin "H3") (pinfunction "DQL4_H3") (pintype "bidirectional"))
    )
    (net (code "33") (name "/DDR_DQ8") (class "Default")
      (node (ref "U1") (pin "R27") (pinfunction "DDR_DQ8_R27") (pintype "passive"))
      (node (ref "U2") (pin "D7") (pinfunction "DQU0_D7") (pintype "bidirectional"))
    )
    (net (code "34") (name "/DDR_DQ9") (class "Default")
      (node (ref "U1") (pin "R26") (pinfunction "DDR_DQ9_R26") (pintype "passive"))
      (node (ref "U2") (pin "A7") (pinfunction "DQU4_A7") (pintype "bidirectional"))
    )
    (net (code "35") (name "/DDR_DQ10") (class "Default")
      (node (ref "U1") (pin "P27") (pinfunction "DDR_DQ10_P27") (pintype "passive"))
      (node (ref "U2") (pin "B8") (pinfunction "DQU6_B8") (pintype "bidirectional"))
    )
    (net (code "36") (name "/DDR_DQ11") (class "Default")
      (node (ref "U1") (pin "P26") (pinfunction "DDR_DQ11_P26") (pintype "passive"))
      (node (ref "U2") (pin "C8") (pinfunction "DQU2_C8") (pintype "bidirectional"))
    )
    (net (code "37") (name "/DDR_DQ12") (class "Default")
      (node (ref "U1") (pin "V26") (pinfunction "DDR_DQ12_V26") (pintype "passive"))
      (node (ref "U2") (pin "C2") (pinfunction "DQU3_C2") (pintype "bidirectional"))
    )
    (net (code "38") (name "/DDR_DQ13") (class "Default")
      (node (ref "U1") (pin "V27") (pinfunction "DDR_DQ13_V27") (pintype "passive"))
      (node (ref "U2") (pin "C3") (pinfunction "DQU1_C3") (pintype "bidirectional"))
    )
    (net (code "39") (name "/DDR_DQ14") (class "Default")
      (node (ref "U1") (pin "V25") (pinfunction "DDR_DQ14_V25") (pintype "passive"))
      (node (ref "U2") (pin "A3") (pinfunction "DQU7_A3") (pintype "bidirectional"))
    )
    (net (code "40") (name "/DDR_DQ15") (class "Default")
      (node (ref "U1") (pin "U25") (pinfunction "DDR_DQ15_U25") (pintype "passive"))
      (node (ref "U2") (pin "A2") (pinfunction "DQU5_A2") (pintype "bidirectional"))
    )
    (net (code "41") (name "/DDR_DQ16") (class "Default")
      (node (ref "U1") (pin "F25") (pinfunction "DDR_DQ16_F25") (pintype "passive"))
      (node (ref "U8") (pin "D7") (pinfunction "DQU0_D7") (pintype "bidirectional"))
    )
    (net (code "42") (name "/DDR_DQ17") (class "Default")
      (node (ref "U1") (pin "E26") (pinfunction "DDR_DQ17_E26") (pintype "passive"))
      (node (ref "U8") (pin "A7") (pinfunction "DQU4_A7") (pintype "bidirectional"))
    )
    (net (code "43") (name "/DDR_DQ18") (class "Default")
      (node (ref "U1") (pin "F24") (pinfunction "DDR_DQ18_F24") (pintype "passive"))
      (node (ref "U8") (pin "B8") (pinfunction "DQU6_B8") (pintype "bidirectional"))
    )
    (net (code "44") (name "/DDR_DQ19") (class "Default")
      (node (ref "U1") (pin "E25") (pinfunction "DDR_DQ19_E25") (pintype "passive"))
      (node (ref "U8") (pin "C8") (pinfunction "DQU2_C8") (pintype "bidirectional"))
    )
    (net (code "45") (name "/DDR_DQ20") (class "Default")
      (node (ref "U1") (pin "J25") (pinfunction "DDR_DQ20_J25") (pintype "passive"))
      (node (ref "U8") (pin "A3") (pinfunction "DQU7_A3") (pintype "bidirectional"))
    )
    (net (code "46") (name "/DDR_DQ21") (class "Default")
      (node (ref "U1") (pin "H25") (pinfunction "DDR_DQ21_H25") (pintype "passive"))
      (node (ref "U8") (pin "C2") (pinfunction "DQU3_C2") (pintype "bidirectional"))
    )
    (net (code "47") (name "/DDR_DQ22") (class "Default")
      (node (ref "U1") (pin "G26") (pinfunction "DDR_DQ22_G26") (pintype "passive"))
      (node (ref "U8") (pin "C3") (pinfunction "DQU1_C3") (pintype "bidirectional"))
    )
    (net (code "48") (name "/DDR_DQ23") (class "Default")
      (node (ref "U1") (pin "G25") (pinfunction "DDR_DQ23_G25") (pintype "passive"))
      (node (ref "U8") (pin "A2") (pinfunction "DQU5_A2") (pintype "bidirectional"))
    )
    (net (code "49") (name "/DDR_DQ24") (class "Default")
      (node (ref "U1") (pin "J26") (pinfunction "DDR_DQ24_J26") (pintype "passive"))
      (node (ref "U8") (pin "F2") (pinfunction "DQL2_F2") (pintype "bidirectional"))
    )
    (net (code "50") (name "/DDR_DQ25") (class "Default")
      (node (ref "U1") (pin "K25") (pinfunction "DDR_DQ25_K25") (pintype "passive"))
      (node (ref "U8") (pin "E3") (pinfunction "DQL0_E3") (pintype "bidirectional"))
    )
    (net (code "51") (name "/DDR_DQ26") (class "Default")
      (node (ref "U1") (pin "K26") (pinfunction "DDR_DQ26_K26") (pintype "passive"))
      (node (ref "U8") (pin "G2") (pinfunction "DQL6_G2") (pintype "bidirectional"))
    )
    (net (code "52") (name "/DDR_DQ27") (class "Default")
      (node (ref "U1") (pin "K27") (pinfunction "DDR_DQ27_K27") (pintype "passive"))
      (node (ref "U8") (pin "H3") (pinfunction "DQL4_H3") (pintype "bidirectional"))
    )
    (net (code "53") (name "/DDR_DQ28") (class "Default")
      (node (ref "U1") (pin "L25") (pinfunction "DDR_DQ28_L25") (pintype "passive"))
      (node (ref "U8") (pin "F7") (pinfunction "DQL1_F7") (pintype "bidirectional"))
    )
    (net (code "54") (name "/DDR_DQ29") (class "Default")
      (node (ref "U1") (pin "N25") (pinfunction "DDR_DQ29_N25") (pintype "passive"))
      (node (ref "U8") (pin "F8") (pinfunction "DQL3_F8") (pintype "bidirectional"))
    )
    (net (code "55") (name "/DDR_DQ30") (class "Default")
      (node (ref "U1") (pin "N26") (pinfunction "DDR_DQ30_N26") (pintype "passive"))
      (node (ref "U8") (pin "H7") (pinfunction "DQL7_H7") (pintype "bidirectional"))
    )
    (net (code "56") (name "/DDR_DQ31") (class "Default")
      (node (ref "U1") (pin "P25") (pinfunction "DDR_DQ31_P25") (pintype "passive"))
      (node (ref "U8") (pin "H8") (pinfunction "DQL5_H8") (pintype "bidirectional"))
    )
    (net (code "57") (name "/DDR_DQM0") (class "Default")
      (node (ref "U1") (pin "AB25") (pinfunction "DDR_DQM0_AB25") (pintype "passive"))
      (node (ref "U2") (pin "E7") (pinfunction "DML_E7") (pintype "input"))
    )
    (net (code "58") (name "/DDR_DQM1") (class "Default")
      (node (ref "U1") (pin "U26") (pinfunction "DDR_DQM1_U26") (pintype "passive"))
      (node (ref "U2") (pin "D3") (pinfunction "DMU_D3") (pintype "input"))
    )
    (net (code "59") (name "/DDR_DQM2") (class "Default")
      (node (ref "U1") (pin "G27") (pinfunction "DDR_DQM2_G27") (pintype "passive"))
      (node (ref "U8") (pin "D3") (pinfunction "DMU_D3") (pintype "input"))
    )
    (net (code "60") (name "/DDR_DQM3") (class "Default")
      (node (ref "U1") (pin "M25") (pinfunction "DDR_DQM3_M25") (pintype "passive"))
      (node (ref "U8") (pin "E7") (pinfunction "DML_E7") (pintype "input"))
    )
    (net (code "61") (name "/DDR_DQS0_N") (class "Default")
      (node (ref "U1") (pin "AA26") (pinfunction "DDR_DQS0N_AA26") (pintype "passive"))
      (node (ref "U2") (pin "G3") (pinfunction "DQSL#_G3") (pintype "bidirectional"))
    )
    (net (code "62") (name "/DDR_DQS0_P") (class "Default")
      (node (ref "U1") (pin "AA25") (pinfunction "DDR_DQS0P_AA25") (pintype "passive"))
      (node (ref "U2") (pin "F3") (pinfunction "DQSL_F3") (pintype "bidirectional"))
    )
    (net (code "63") (name "/DDR_DQS1_N") (class "Default")
      (node (ref "U1") (pin "R25") (pinfunction "DDR_DQS1N_R25") (pintype "passive"))
      (node (ref "U2") (pin "B7") (pinfunction "DQSU#_B7") (pintype "bidirectional"))
    )
    (net (code "64") (name "/DDR_DQS1_P") (class "Default")
      (node (ref "U1") (pin "T25") (pinfunction "DDR_DQS1P_T25") (pintype "passive"))
      (node (ref "U2") (pin "C7") (pinfunction "DQSU_C7") (pintype "bidirectional"))
    )
    (net (code "65") (name "/DDR_DQS2_N") (class "Default")
      (node (ref "U1") (pin "F26") (pinfunction "DDR_DQS2N_F26") (pintype "passive"))
      (node (ref "U8") (pin "B7") (pinfunction "DQSU#_B7") (pintype "bidirectional"))
    )
    (net (code "66") (name "/DDR_DQS2_P") (class "Default")
      (node (ref "U1") (pin "F27") (pinfunction "DDR_DQS2P_F27") (pintype "passive"))
      (node (ref "U8") (pin "C7") (pinfunction "DQSU_C7") (pintype "bidirectional"))
    )
    (net (code "67") (name "/DDR_DQS3_N") (class "Default")
      (node (ref "U1") (pin "L27") (pinfunction "DDR_DQS3N_L27") (pintype "passive"))
      (node (ref "U8") (pin "G3") (pinfunction "DQSL#_G3") (pintype "bidirectional"))
    )
    (net (code "68") (name "/DDR_DQS3_P") (class "Default")
      (node (ref "U1") (pin "L26") (pinfunction "DDR_DQS3P_L26") (pintype "passive"))
      (node (ref "U8") (pin "F3") (pinfunction "DQSL_F3") (pintype "bidirectional"))
    )
    (net (code "69") (name "/DDR_ODT") (class "Default")
      (node (ref "R140") (pin "1") (pinfunction "1_1") (pintype "passive"))
      (node (ref "U1") (pin "P22") (pinfunction "DDR_A3_P22") (pintype "passive"))
      (node (ref "U2") (pin "K1") (pinfunction "ODT_K1") (pintype "input"))
      (node (ref "U8") (pin "K1") (pinfunction "ODT_K1") (pintype "input"))
    )
    (net (code "70") (name "/DDR_RASN") (class "Default")
      (node (ref "R135") (pin "1") (pinfunction "1_1") (pintype "passive"))
      (node (ref "U1") (pin "P24") (pinfunction "DDR_A11_P24") (pintype "passive"))
      (node (ref "U2") (pin "J3") (pinfunction "RAS#_J3") (pintype "input"))
      (node (ref "U8") (pin "J3") (pinfunction "RAS#_J3") (pintype "input"))
    )
    (net (code "71") (name "/DDR_RESETN") (class "Default")
      (node (ref "R156") (pin "2") (pinfunction "2_2") (pintype "passive"))
      (node (ref "U1") (pin "E21") (pinfunction "DDR_RESETN_E21") (pintype "passive"))
      (node (ref "U2") (pin "T2") (pinfunction "RESET#_T2") (pintype "input"))
      (node (ref "U8") (pin "T2") (pinfunction "RESET#_T2") (pintype "input"))
    )
    (net (code "72") (name "/DDR_WEN") (class "Default")
      (node (ref "R139") (pin "1") (pinfunction "1_1") (pintype "passive"))
      (node (ref "U1") (pin "M24") (pinfunction "DDR_A14_M24") (pintype "passive"))
      (node (ref "U2") (pin "L3") (pinfunction "WE#_L3") (pintype "input"))
      (node (ref "U8") (pin "L3") (pinfunction "WE#_L3") (pintype "input"))
    )
    (net (code "73") (name "GND") (class "Default")
      (node (ref "C100") (pin "1") (pinfunction "1_1") (pintype "passive"))
      (node (ref "C101") (pin "1") (pinfunction "1_1") (pintype "passive"))
      (node (ref "C102") (pin "1") (pinfunction "1_1") (pintype "passive"))
      (node (ref "C103") (pin "1") (pinfunction "1_1") (pintype "passive"))
      (node (ref "C104") (pin "1") (pinfunction "1_1") (pintype "passive"))
      (node (ref "C105") (pin "1") (pinfunction "1_1") (pintype "passive"))
      (node (ref "C106") (pin "1") (pinfunction "1_1") (pintype "passive"))
      (node (ref "C107") (pin "1") (pinfunction "1_1") (pintype "passive"))
      (node (ref "C108") (pin "1") (pinfunction "1_1") (pintype "passive"))
      (node (ref "C109") (pin "1") (pinfunction "1_1") (pintype "passive"))
      (node (ref "C110") (pin "1") (pinfunction "1_1") (pintype "passive"))
      (node (ref "C111") (pin "1") (pinfunction "1_1") (pintype "passive"))
      (node (ref "C112") (pin "1") (pinfunction "1_1") (pintype "passive"))
      (node (ref "C113") (pin "1") (pinfunction "1_1") (pintype "passive"))
      (node (ref "C114") (pin "1") (pinfunction "1_1") (pintype "passive"))
      (node (ref "C115") (pin "1") (pinfunction "1_1") (pintype "passive"))
      (node (ref "C116") (pin "1") (pinfunction "1_1") (pintype "passive"))
      (node (ref "C119") (pin "1") (pinfunction "1_1") (pintype "passive"))
      (node (ref "C120") (pin "1") (pinfunction "1_1") (pintype "passive"))
      (node (ref "C121") (pin "1") (pinfunction "1_1") (pintype "passive"))
      (node (ref "C122") (pin "1") (pinfunction "1_1") (pintype "passive"))
      (node (ref "C123") (pin "1") (pinfunction "1_1") (pintype "passive"))
      (node (ref "C124") (pin "1") (pinfunction "1_1") (pintype "passive"))
      (node (ref "C125") (pin "1") (pinfunction "1_1") (pintype "passive"))
      (node (ref "C126") (pin "1") (pinfunction "1_1") (pintype "passive"))
      (node (ref "C127") (pin "1") (pinfunction "1_1") (pintype "passive"))
      (node (ref "C129") (pin "1") (pinfunction "1_1") (pintype "passive"))
      (node (ref "C131") (pin "1") (pinfunction "1_1") (pintype "passive"))
      (node (ref "C132") (pin "1") (pinfunction "1_1") (pintype "passive"))
      (node (ref "C133") (pin "1") (pinfunction "1_1") (pintype "passive"))
      (node (ref "C134") (pin "1") (pinfunction "1_1") (pintype "passive"))
      (node (ref "C135") (pin "1") (pinfunction "1_1") (pintype "passive"))
      (node (ref "C136") (pin "1") (pinfunction "1_1") (pintype "passive"))
      (node (ref "C137") (pin "1") (pinfunction "1_1") (pintype "passive"))
      (node (ref "C138") (pin "1") (pinfunction "1_1") (pintype "passive"))
      (node (ref "C139") (pin "1") (pinfunction "1_1") (pintype "passive"))
      (node (ref "C140") (pin "1") (pinfunction "1_1") (pintype "passive"))
      (node (ref "C146") (pin "1") (pinfunction "1_1") (pintype "passive"))
      (node (ref "C167") (pin "1") (pinfunction "1_1") (pintype "passive"))
      (node (ref "C177") (pin "1") (pinfunction "1_1") (pintype "passive"))
      (node (ref "R1") (pin "1") (pinfunction "1_1") (pintype "passive"))
      (node (ref "R142") (pin "1") (pinfunction "1_1") (pintype "passive"))
      (node (ref "R144") (pin "1") (pinfunction "1_1") (pintype "passive"))
      (node (ref "R145") (pin "1") (pinfunction "1_1") (pintype "passive"))
      (node (ref "R147") (pin "1") (pinfunction "1_1") (pintype "passive"))
      (node (ref "R149") (pin "1") (pinfunction "1_1") (pintype "passive"))
      (node (ref "R150") (pin "1") (pinfunction "1_1") (pintype "passive"))
      (node (ref "R156") (pin "1") (pinfunction "1_1") (pintype "passive"))
      (node (ref "U2") (pin "A9") (pinfunction "VSS_A9") (pintype "power_in"))
      (node (ref "U2") (pin "B1") (pinfunction "VSSQ_B1") (pintype "power_in"))
      (node (ref "U2") (pin "B3") (pinfunction "VSS_B3") (pintype "power_in"))
      (node (ref "U2") (pin "B9") (pinfunction "VSSQ_B9") (pintype "power_in"))
      (node (ref "U2") (pin "D1") (pinfunction "VSSQ_D1") (pintype "power_in"))
      (node (ref "U2") (pin "D8") (pinfunction "VSSQ_D8") (pintype "power_in"))
      (node (ref "U2") (pin "E1") (pinfunction "VSS_E1") (pintype "power_in"))
      (node (ref "U2") (pin "E2") (pinfunction "VSSQ_E2") (pintype "power_in"))
      (node (ref "U2") (pin "E8") (pinfunction "VSSQ_E8") (pintype "power_in"))
      (node (ref "U2") (pin "F9") (pinfunction "VSSQ_F9") (pintype "power_in"))
      (node (ref "U2") (pin "G1") (pinfunction "VSSQ_G1") (pintype "power_in"))
      (node (ref "U2") (pin "G8") (pinfunction "VSS_G8") (pintype "power_in"))
      (node (ref "U2") (pin "G9") (pinfunction "VSSQ_G9") (pintype "power_in"))
      (node (ref "U2") (pin "J2") (pinfunction "VSS_J2") (pintype "power_in"))
      (node (ref "U2") (pin "J8") (pinfunction "VSS_J8") (pintype "power_in"))
      (node (ref "U2") (pin "M1") (pinfunction "VSS_M1") (pintype "power_in"))
      (node (ref "U2") (pin "M9") (pinfunction "VSS_M9") (pintype "power_in"))
      (node (ref "U2") (pin "P1") (pinfunction "VSS_P1") (pintype "power_in"))
      (node (ref "U2") (pin "P9") (pinfunction "VSS_P9") (pintype "power_in"))
      (node (ref "U2") (pin "T1") (pinfunction "VSS_T1") (pintype "power_in"))
      (node (ref "U2") (pin "T9") (pinfunction "VSS_T9") (pintype "power_in"))
      (node (ref "U8") (pin "A9") (pinfunction "VSS_A9") (pintype "power_in"))
      (node (ref "U8") (pin "B1") (pinfunction "VSSQ_B1") (pintype "power_in"))
      (node (ref "U8") (pin "B3") (pinfunction "VSS_B3") (pintype "power_in"))
      (node (ref "U8") (pin "B9") (pinfunction "VSSQ_B9") (pintype "power_in"))
      (node (ref "U8") (pin "D1") (pinfunction "VSSQ_D1") (pintype "power_in"))
      (node (ref "U8") (pin "D8") (pinfunction "VSSQ_D8") (pintype "power_in"))
      (node (ref "U8") (pin "E1") (pinfunction "VSS_E1") (pintype "power_in"))
      (node (ref "U8") (pin "E2") (pinfunction "VSSQ_E2") (pintype "power_in"))
      (node (ref "U8") (pin "E8") (pinfunction "VSSQ_E8") (pintype "power_in"))
      (node (ref "U8") (pin "F9") (pinfunction "VSSQ_F9") (pintype "power_in"))
      (node (ref "U8") (pin "G1") (pinfunction "VSSQ_G1") (pintype "power_in"))
      (node (ref "U8") (pin "G8") (pinfunction "VSS_G8") (pintype "power_in"))
      (node (ref "U8") (pin "G9") (pinfunction "VSSQ_G9") (pintype "power_in"))
      (node (ref "U8") (pin "J2") (pinfunction "VSS_J2") (pintype "power_in"))
      (node (ref "U8") (pin "J8") (pinfunction "VSS_J8") (pintype "power_in"))
      (node (ref "U8") (pin "M1") (pinfunction "VSS_M1") (pintype "power_in"))
      (node (ref "U8") (pin "M9") (pinfunction "VSS_M9") (pintype "power_in"))
      (node (ref "U8") (pin "P1") (pinfunction "VSS_P1") (pintype "power_in"))
      (node (ref "U8") (pin "P9") (pinfunction "VSS_P9") (pintype "power_in"))
      (node (ref "U8") (pin "T1") (pinfunction "VSS_T1") (pintype "power_in"))
      (node (ref "U8") (pin "T9") (pinfunction "VSS_T9") (pintype "power_in"))
    )
    (net (code "74") (name "Net-(U1F-DDR_ZQ)") (class "Default")
      (node (ref "R1") (pin "2") (pinfunction "2_2") (pintype "passive"))
      (node (ref "U1") (pin "K22") (pinfunction "DDR_ZQ_K22") (pintype "passive"))
    )
    (net (code "75") (name "Net-(U2-VREFCA)") (class "Default")
      (node (ref "C137") (pin "2") (pinfunction "2_2") (pintype "passive"))
      (node (ref "R143") (pin "1") (pinfunction "1_1") (pintype "passive"))
      (node (ref "R144") (pin "2") (pinfunction "2_2") (pintype "passive"))
      (node (ref "U2") (pin "M8") (pinfunction "VREFCA_M8") (pintype "passive"))
    )
    (net (code "76") (name "Net-(U2-VREFDQ)") (class "Default")
      (node (ref "C138") (pin "2") (pinfunction "2_2") (pintype "passive"))
      (node (ref "R141") (pin "1") (pinfunction "1_1") (pintype "passive"))
      (node (ref "R142") (pin "2") (pinfunction "2_2") (pintype "passive"))
      (node (ref "U2") (pin "H1") (pinfunction "VREFDQ_H1") (pintype "passive"))
    )
    (net (code "77") (name "Net-(U2-ZQ)") (class "Default")
      (node (ref "R145") (pin "2") (pinfunction "2_2") (pintype "passive"))
      (node (ref "U2") (pin "L8") (pinfunction "ZQ_L8") (pintype "passive"))
    )
    (net (code "78") (name "Net-(U8-VREFCA)") (class "Default")
      (node (ref "C120") (pin "2") (pinfunction "2_2") (pintype "passive"))
      (node (ref "R148") (pin "1") (pinfunction "1_1") (pintype "passive"))
      (node (ref "R149") (pin "2") (pinfunction "2_2") (pintype "passive"))
      (node (ref "U8") (pin "M8") (pinfunction "VREFCA_M8") (pintype "passive"))
    )
    (net (code "79") (name "Net-(U8-VREFDQ)") (class "Default")
      (node (ref "C121") (pin "2") (pinfunction "2_2") (pintype "passive"))
      (node (ref "R146") (pin "1") (pinfunction "1_1") (pintype "passive"))
      (node (ref "R147") (pin "2") (pinfunction "2_2") (pintype "passive"))
      (node (ref "U8") (pin "H1") (pinfunction "VREFDQ_H1") (pintype "passive"))
    )
    (net (code "80") (name "Net-(U8-ZQ)") (class "Default")
      (node (ref "R150") (pin "2") (pinfunction "2_2") (pintype "passive"))
      (node (ref "U8") (pin "L8") (pinfunction "ZQ_L8") (pintype "passive"))
    )
    (net (code "81") (name "VDD_DDR") (class "Default")
      (node (ref "C100") (pin "2") (pinfunction "2_2") (pintype "passive"))
      (node (ref "C101") (pin "2") (pinfunction "2_2") (pintype "passive"))
      (node (ref "C102") (pin "2") (pinfunction "2_2") (pintype "passive"))
      (node (ref "C103") (pin "2") (pinfunction "2_2") (pintype "passive"))
      (node (ref "C104") (pin "2") (pinfunction "2_2") (pintype "passive"))
      (node (ref "C105") (pin "2") (pinfunction "2_2") (pintype "passive"))
      (node (ref "C106") (pin "2") (pinfunction "2_2") (pintype "passive"))
      (node (ref "C107") (pin "2") (pinfunction "2_2") (pintype "passive"))
      (node (ref "C108") (pin "2") (pinfunction "2_2") (pintype "passive"))
      (node (ref "C109") (pin "2") (pinfunction "2_2") (pintype "passive"))
      (node (ref "C110") (pin "2") (pinfunction "2_2") (pintype "passive"))
      (node (ref "C111") (pin "2") (pinfunction "2_2") (pintype "passive"))
      (node (ref "C112") (pin "2") (pinfunction "2_2") (pintype "passive"))
      (node (ref "C113") (pin "2") (pinfunction "2_2") (pintype "passive"))
      (node (ref "C114") (pin "2") (pinfunction "2_2") (pintype "passive"))
      (node (ref "C115") (pin "2") (pinfunction "2_2") (pintype "passive"))
      (node (ref "C116") (pin "2") (pinfunction "2_2") (pintype "passive"))
      (node (ref "C119") (pin "2") (pinfunction "2_2") (pintype "passive"))
      (node (ref "C146") (pin "2") (pinfunction "2_2") (pintype "passive"))
      (node (ref "C167") (pin "2") (pinfunction "2_2") (pintype "passive"))
      (node (ref "C177") (pin "2") (pinfunction "2_2") (pintype "passive"))
      (node (ref "R141") (pin "2") (pinfunction "2_2") (pintype "passive"))
      (node (ref "R143") (pin "2") (pinfunction "2_2") (pintype "passive"))
      (node (ref "R146") (pin "2") (pinfunction "2_2") (pintype "passive"))
      (node (ref "R148") (pin "2") (pinfunction "2_2") (pintype "passive"))
      (node (ref "U2") (pin "A1") (pinfunction "VDDQ_A1") (pintype "power_in"))
      (node (ref "U2") (pin "A8") (pinfunction "VDDQ_A8") (pintype "power_in"))
      (node (ref "U2") (pin "B2") (pinfunction "VDD_B2") (pintype "power_in"))
      (node (ref "U2") (pin "C1") (pinfunction "VDDQ_C1") (pintype "power_in"))
      (node (ref "U2") (pin "C9") (pinfunction "VDDQ_C9") (pintype "power_in"))
      (node (ref "U2") (pin "D2") (pinfunction "VDDQ_D2") (pintype "power_in"))
      (node (ref "U2") (pin "D9") (pinfunction "VDD_D9") (pintype "power_in"))
      (node (ref "U2") (pin "E9") (pinfunction "VDDQ_E9") (pintype "power_in"))
      (node (ref "U2") (pin "F1") (pinfunction "VDDQ_F1") (pintype "power_in"))
      (node (ref "U2") (pin "G7") (pinfunction "VDD_G7") (pintype "power_in"))
      (node (ref "U2") (pin "H2") (pinfunction "VDDQ_H2") (pintype "power_in"))
      (node (ref "U2") (pin "H9") (pinfunction "VDDQ_H9") (pintype "power_in"))
      (node (ref "U2") (pin "K2") (pinfunction "VDD_K2") (pintype "power_in"))
      (node (ref "U2") (pin "K8") (pinfunction "VDD_K8") (pintype "power_in"))
      (node (ref "U2") (pin "N1") (pinfunction "VDD_N1") (pintype "power_in"))
      (node (ref "U2") (pin "N9") (pinfunction "VDD_N9") (pintype "power_in"))
      (node (ref "U2") (pin "R1") (pinfunction "VDD_R1") (pintype "power_in"))
      (node (ref "U2") (pin "R9") (pinfunction "VDD_R9") (pintype "power_in"))
      (node (ref "U8") (pin "A1") (pinfunction "VDDQ_A1") (pintype "power_in"))
      (node (ref "U8") (pin "A8") (pinfunction "VDDQ_A8") (pintype "power_in"))
      (node (ref "U8") (pin "B2") (pinfunction "VDD_B2") (pintype "power_in"))
      (node (ref "U8") (pin "C1") (pinfunction "VDDQ_C1") (pintype "power_in"))
      (node (ref "U8") (pin "C9") (pinfunction "VDDQ_C9") (pintype "power_in"))
      (node (ref "U8") (pin "D2") (pinfunction "VDDQ_D2") (pintype "power_in"))
      (node (ref "U8") (pin "D9") (pinfunction "VDD_D9") (pintype "power_in"))
      (node (ref "U8") (pin "E9") (pinfunction "VDDQ_E9") (pintype "power_in"))
      (node (ref "U8") (pin "F1") (pinfunction "VDDQ_F1") (pintype "power_in"))
      (node (ref "U8") (pin "G7") (pinfunction "VDD_G7") (pintype "power_in"))
      (node (ref "U8") (pin "H2") (pinfunction "VDDQ_H2") (pintype "power_in"))
      (node (ref "U8") (pin "H9") (pinfunction "VDDQ_H9") (pintype "power_in"))
      (node (ref "U8") (pin "K2") (pinfunction "VDD_K2") (pintype "power_in"))
      (node (ref "U8") (pin "K8") (pinfunction "VDD_K8") (pintype "power_in"))
      (node (ref "U8") (pin "N1") (pinfunction "VDD_N1") (pintype "power_in"))
      (node (ref "U8") (pin "N9") (pinfunction "VDD_N9") (pintype "power_in"))
      (node (ref "U8") (pin "R1") (pinfunction "VDD_R1") (pintype "power_in"))
      (node (ref "U8") (pin "R9") (pinfunction "VDD_R9") (pintype "power_in"))
    )
    (net (code "82") (name "VTT_DDR") (class "Default")
      (node (ref "C122") (pin "2") (pinfunction "2_2") (pintype "passive"))
      (node (ref "C123") (pin "2") (pinfunction "2_2") (pintype "passive"))
      (node (ref "C124") (pin "2") (pinfunction "2_2") (pintype "passive"))
      (node (ref "C125") (pin "2") (pinfunction "2_2") (pintype "passive"))
      (node (ref "C126") (pin "2") (pinfunction "2_2") (pintype "passive"))
      (node (ref "C127") (pin "2") (pinfunction "2_2") (pintype "passive"))
      (node (ref "C129") (pin "2") (pinfunction "2_2") (pintype "passive"))
      (node (ref "C131") (pin "2") (pinfunction "2_2") (pintype "passive"))
      (node (ref "C132") (pin "2") (pinfunction "2_2") (pintype "passive"))
      (node (ref "C133") (pin "2") (pinfunction "2_2") (pintype "passive"))
      (node (ref "C134") (pin "2") (pinfunction "2_2") (pintype "passive"))
      (node (ref "C135") (pin "2") (pinfunction "2_2") (pintype "passive"))
      (node (ref "C136") (pin "2") (pinfunction "2_2") (pintype "passive"))
      (node (ref "C139") (pin "2") (pinfunction "2_2") (pintype "passive"))
      (node (ref "C140") (pin "2") (pinfunction "2_2") (pintype "passive"))
      (node (ref "R116") (pin "2") (pinfunction "2_2") (pintype "passive"))
      (node (ref "R117") (pin "2") (pinfunction "2_2") (pintype "passive"))
      (node (ref "R118") (pin "2") (pinfunction "2_2") (pintype "passive"))
      (node (ref "R119") (pin "2") (pinfunction "2_2") (pintype "passive"))
      (node (ref "R120") (pin "2") (pinfunction "2_2") (pintype "passive"))
      (node (ref "R121") (pin "2") (pinfunction "2_2") (pintype "passive"))
      (node (ref "R122") (pin "2") (pinfunction "2_2") (pintype "passive"))
      (node (ref "R123") (pin "2") (pinfunction "2_2") (pintype "passive"))
      (node (ref "R124") (pin "2") (pinfunction "2_2") (pintype "passive"))
      (node (ref "R125") (pin "2") (pinfunction "2_2") (pintype "passive"))
      (node (ref "R126") (pin "2") (pinfunction "2_2") (pintype "passive"))
      (node (ref "R127") (pin "2") (pinfunction "2_2") (pintype "passive"))
      (node (ref "R128") (pin "2") (pinfunction "2_2") (pintype "passive"))
      (node (ref "R129") (pin "2") (pinfunction "2_2") (pintype "passive"))
      (node (ref "R130") (pin "2") (pinfunction "2_2") (pintype "passive"))
      (node (ref "R131") (pin "2") (pinfunction "2_2") (pintype "passive"))
      (node (ref "R132") (pin "2") (pinfunction "2_2") (pintype "passive"))
      (node (ref "R133") (pin "2") (pinfunction "2_2") (pintype "passive"))
      (node (ref "R134") (pin "2") (pinfunction "2_2") (pintype "passive"))
      (node (ref "R135") (pin "2") (pinfunction "2_2") (pintype "passive"))
      (node (ref "R136") (pin "2") (pinfunction "2_2") (pintype "passive"))
      (node (ref "R137") (pin "2") (pinfunction "2_2") (pintype "passive"))
      (node (ref "R138") (pin "2") (pinfunction "2_2") (pintype "passive"))
      (node (ref "R139") (pin "2") (pinfunction "2_2") (pintype "passive"))
      (node (ref "R140") (pin "2") (pinfunction "2_2") (pintype "passive"))
    )
    (net (code "83") (name "unconnected-(U1F-DDR_A1-PadAD25)") (class "Default")
      (node (ref "U1") (pin "AD25") (pinfunction "DDR_A1_AD25") (pintype "passive+no_connect"))
    )
    (net (code "84") (name "unconnected-(U1F-DDR_A6-PadY24)") (class "Default")
      (node (ref "U1") (pin "Y24") (pinfunction "DDR_A6_Y24") (pintype "passive+no_connect"))
    )
    (net (code "85") (name "unconnected-(U1F-DDR_A7-PadAC25)") (class "Default")
      (node (ref "U1") (pin "AC25") (pinfunction "DDR_A7_AC25") (pintype "passive+no_connect"))
    )
    (net (code "86") (name "unconnected-(U1F-DDR_A19-PadL21)") (class "Default")
      (node (ref "U1") (pin "L21") (pinfunction "DDR_A19_L21") (pintype "passive+no_connect"))
    )
    (net (code "87") (name "unconnected-(U1F-DDR_VREF-PadG21)") (class "Default")
      (node (ref "U1") (pin "G21") (pinfunction "DDR_VREF_G21") (pintype "passive+no_connect"))
    )
    (net (code "88") (name "unconnected-(U2-NC-PadJ1)") (class "Default")
      (node (ref "U2") (pin "J1") (pinfunction "NC_J1") (pintype "passive+no_connect"))
    )
    (net (code "89") (name "unconnected-(U2-NC-PadJ9)") (class "Default")
      (node (ref "U2") (pin "J9") (pinfunction "NC_J9") (pintype "passive+no_connect"))
    )
    (net (code "90") (name "unconnected-(U2-NC-PadL1)") (class "Default")
      (node (ref "U2") (pin "L1") (pinfunction "NC_L1") (pintype "passive+no_connect"))
    )
    (net (code "91") (name "unconnected-(U2-NC-PadL9)") (class "Default")
      (node (ref "U2") (pin "L9") (pinfunction "NC_L9") (pintype "passive+no_connect"))
    )
    (net (code "92") (name "unconnected-(U8-NC-PadJ1)") (class "Default")
      (node (ref "U8") (pin "J1") (pinfunction "NC_J1") (pintype "passive+no_connect"))
    )
    (net (code "93") (name "unconnected-(U8-NC-PadJ9)") (class "Default")
      (node (ref "U8") (pin "J9") (pinfunction "NC_J9") (pintype "passive+no_connect"))
    )
    (net (code "94") (name "unconnected-(U8-NC-PadL1)") (class "Default")
      (node (ref "U8") (pin "L1") (pinfunction "NC_L1") (pintype "passive+no_connect"))
    )
    (net (code "95") (name "unconnected-(U8-NC-PadL9)") (class "Default")
      (node (ref "U8") (pin "L9") (pinfunction "NC_L9") (pintype "passive+no_connect"))
    )
  )
)
